# MAX3738ETG_MB.net
KiCad netlist of a schematic drawn in Altium Designer
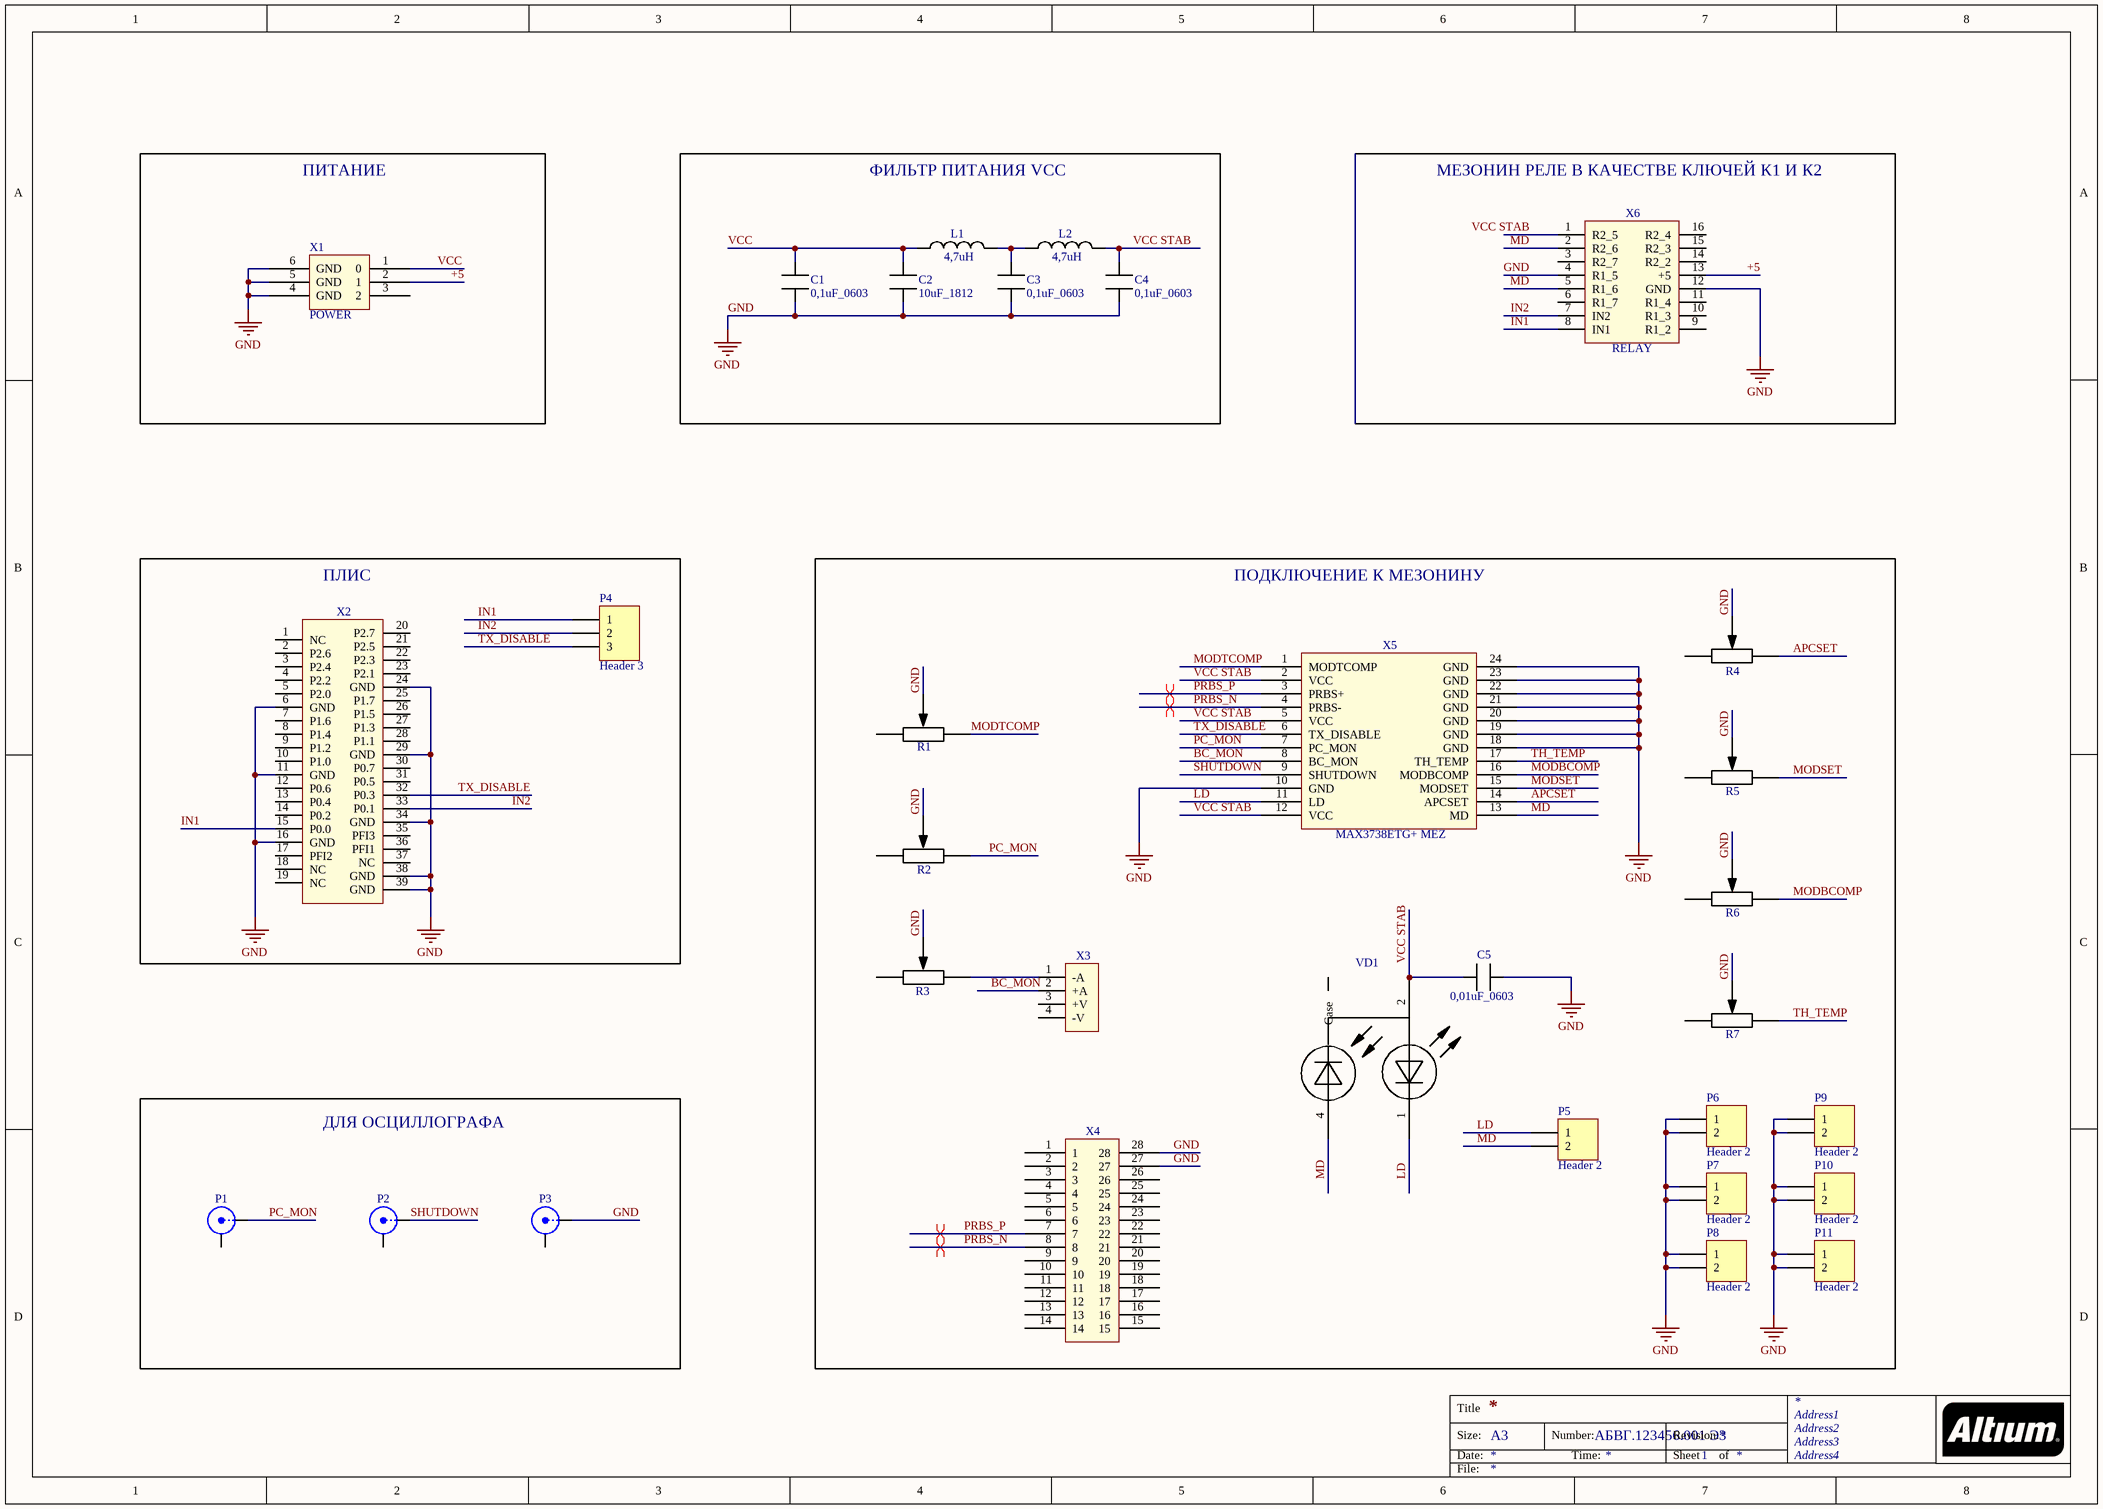
[diagram p0: MAX3738ETG+ MB.SchDoc]

(export (version "E")
  (design (tool "Eeschema 10.0.6"))
  (components
    (comp (ref "C1")
      (value "0,1uF_0603")
      (footprint "aab_Passive:CAP_0603")
      (libsource (lib "aab_Schlib") (part "CAP"))
    )
    (comp (ref "C2")
      (value "10uF_1812")
      (footprint "aab_Passive:CAP_1812")
      (libsource (lib "aab_Schlib") (part "CAP"))
    )
    (comp (ref "C3")
      (value "0,1uF_0603")
      (footprint "aab_Passive:CAP_0603")
      (libsource (lib "aab_Schlib") (part "CAP"))
    )
    (comp (ref "C4")
      (value "0,1uF_0603")
      (footprint "aab_Passive:CAP_0603")
      (libsource (lib "aab_Schlib") (part "CAP"))
    )
    (comp (ref "C5")
      (value "0,01uF_0603")
      (footprint "aab_Passive:CAP_0603")
      (libsource (lib "aab_Schlib") (part "CAP"))
    )
    (comp (ref "L1")
      (value "4,7uH")
      (footprint "aab_Passive:IND_0805")
      (libsource (lib "aab_Schlib") (part "IND"))
    )
    (comp (ref "L2")
      (value "4,7uH")
      (footprint "aab_Passive:IND_0805")
      (libsource (lib "aab_Schlib") (part "IND"))
    )
    (comp (ref "P1")
      (value "BNC")
      (footprint "BNC_RA CON")
      (description "BNC Elbow Connector")
      (fields (field (name "PUBLISHER") "Altium Limited"))
      (libsource (lib "Miscellaneous Connectors") (part "BNC"))
    )
    (comp (ref "P2")
      (value "BNC")
      (footprint "BNC_RA CON")
      (description "BNC Elbow Connector")
      (fields (field (name "PUBLISHER") "Altium Limited"))
      (libsource (lib "Miscellaneous Connectors") (part "BNC"))
    )
    (comp (ref "P3")
      (value "BNC")
      (footprint "BNC_RA CON")
      (description "BNC Elbow Connector")
      (fields (field (name "PUBLISHER") "Altium Limited"))
      (libsource (lib "Miscellaneous Connectors") (part "BNC"))
    )
    (comp (ref "P4")
      (value "Header 3")
      (footprint "HDR1X3")
      (description "Header, 3-Pin")
      (fields (field (name "PUBLISHER") "Altium Limited"))
      (libsource (lib "Miscellaneous Connectors") (part "Header 3"))
    )
    (comp (ref "P5")
      (value "Header 2")
      (footprint "HDR1X2")
      (description "Header, 2-Pin")
      (fields (field (name "PUBLISHER") "Altium Limited"))
      (libsource (lib "Miscellaneous Connectors") (part "Header 2"))
    )
    (comp (ref "P6")
      (value "Header 2")
      (footprint "HDR1X2")
      (description "Header, 2-Pin")
      (fields (field (name "PUBLISHER") "Altium Limited"))
      (libsource (lib "Miscellaneous Connectors") (part "Header 2"))
    )
    (comp (ref "P7")
      (value "Header 2")
      (footprint "HDR1X2")
      (description "Header, 2-Pin")
      (fields (field (name "PUBLISHER") "Altium Limited"))
      (libsource (lib "Miscellaneous Connectors") (part "Header 2"))
    )
    (comp (ref "P8")
      (value "Header 2")
      (footprint "HDR1X2")
      (description "Header, 2-Pin")
      (fields (field (name "PUBLISHER") "Altium Limited"))
      (libsource (lib "Miscellaneous Connectors") (part "Header 2"))
    )
    (comp (ref "P9")
      (value "Header 2")
      (footprint "HDR1X2")
      (description "Header, 2-Pin")
      (fields (field (name "PUBLISHER") "Altium Limited"))
      (libsource (lib "Miscellaneous Connectors") (part "Header 2"))
    )
    (comp (ref "P10")
      (value "Header 2")
      (footprint "HDR1X2")
      (description "Header, 2-Pin")
      (fields (field (name "PUBLISHER") "Altium Limited"))
      (libsource (lib "Miscellaneous Connectors") (part "Header 2"))
    )
    (comp (ref "P11")
      (value "Header 2")
      (footprint "HDR1X2")
      (description "Header, 2-Pin")
      (fields (field (name "PUBLISHER") "Altium Limited"))
      (libsource (lib "Miscellaneous Connectors") (part "Header 2"))
    )
    (comp (ref "R1")
      (value "RES 3266W")
      (footprint "aab_Passive:RES 3266W")
      (libsource (lib "aab_Schlib") (part "RES 3266W"))
    )
    (comp (ref "R2")
      (value "RES 3266W")
      (footprint "aab_Passive:RES 3266W")
      (libsource (lib "aab_Schlib") (part "RES 3266W"))
    )
    (comp (ref "R3")
      (value "RES 3266W")
      (footprint "aab_Passive:RES 3266W")
      (libsource (lib "aab_Schlib") (part "RES 3266W"))
    )
    (comp (ref "R4")
      (value "RES 3266W")
      (footprint "aab_Passive:RES 3266W")
      (libsource (lib "aab_Schlib") (part "RES 3266W"))
    )
    (comp (ref "R5")
      (value "RES 3266W")
      (footprint "aab_Passive:RES 3266W")
      (libsource (lib "aab_Schlib") (part "RES 3266W"))
    )
    (comp (ref "R6")
      (value "RES 3266W")
      (footprint "aab_Passive:RES 3266W")
      (libsource (lib "aab_Schlib") (part "RES 3266W"))
    )
    (comp (ref "R7")
      (value "RES 3266W")
      (footprint "aab_Passive:RES 3266W")
      (libsource (lib "aab_Schlib") (part "RES 3266W"))
    )
    (comp (ref "VD1")
      (value "LD with MD")
      (footprint "vpl_Passive:AMP_VOLTMETER")
      (libsource (lib "aab_Schlib") (part "LD with MD"))
    )
    (comp (ref "X1") (value "POWER") (footprint "POWER") (libsource (lib "vpl_Schlib") (part "POWER")))
    (comp (ref "X2")
      (value "CHEAP_CON_37_FEMALE")
      (footprint "CHEAP_CONN_FEMALE")
      (libsource (lib "vpl_Schlib") (part "CHEAP_CON_37_FEMALE"))
    )
    (comp (ref "X3")
      (value "AMPVOLT")
      (footprint "AMP_VOLTMETER")
      (libsource (lib "vpl_Schlib") (part "AMP_VOLTMETER"))
    )
    (comp (ref "X4")
      (value "DHR-26F")
      (footprint "aab_Passive:DHR-26F")
      (libsource (lib "aab_Schlib") (part "DHR-26F"))
    )
    (comp (ref "X5")
      (value "MAX3738ETG+ MEZ")
      (footprint "aab_Active:MAX3738ETG+ MEZ")
      (libsource (lib "aab_Schlib") (part "MAX3738ETG+ MEZ"))
    )
    (comp (ref "X6")
      (value "RELAY")
      (footprint "RELAY_MODULE")
      (libsource (lib "vpl_Schlib") (part "MEZON_RELAY"))
    )
  )
  (nets
    (net (code "1") (name "/+5") (class "Default")
      (node (ref "X1") (pin "2") (pinfunction "1_2") (pintype "passive"))
      (node (ref "X6") (pin "13") (pinfunction "+5_13") (pintype "passive"))
    )
    (net (code "2") (name "/APCSET") (class "Default")
      (node (ref "R4") (pin "3") (pinfunction "3_3") (pintype "passive"))
      (node (ref "X5") (pin "14") (pinfunction "APCSET_14") (pintype "passive"))
    )
    (net (code "3") (name "/BC_MON") (class "Default")
      (node (ref "X3") (pin "2") (pinfunction "+A_2") (pintype "passive"))
      (node (ref "X5") (pin "8") (pinfunction "BC_MON_8") (pintype "passive"))
    )
    (net (code "4") (name "/IN1") (class "Default")
      (node (ref "P4") (pin "1") (pinfunction "1_1") (pintype "passive"))
      (node (ref "X2") (pin "15") (pinfunction "P0.0_15") (pintype "passive"))
      (node (ref "X6") (pin "8") (pinfunction "IN1_8") (pintype "passive"))
    )
    (net (code "5") (name "/IN2") (class "Default")
      (node (ref "P4") (pin "2") (pinfunction "2_2") (pintype "passive"))
      (node (ref "X2") (pin "33") (pinfunction "P0.1_33") (pintype "passive"))
      (node (ref "X6") (pin "7") (pinfunction "IN2_7") (pintype "passive"))
    )
    (net (code "6") (name "/LD") (class "Default")
      (node (ref "P5") (pin "1") (pinfunction "1_1") (pintype "passive"))
      (node (ref "VD1") (pin "1") (pinfunction "1_1") (pintype "passive"))
      (node (ref "X5") (pin "11") (pinfunction "LD_11") (pintype "passive"))
    )
    (net (code "7") (name "/MD") (class "Default")
      (node (ref "P5") (pin "2") (pinfunction "2_2") (pintype "passive"))
      (node (ref "VD1") (pin "4") (pinfunction "4_4") (pintype "passive"))
      (node (ref "X5") (pin "13") (pinfunction "MD_13") (pintype "passive"))
      (node (ref "X6") (pin "2") (pinfunction "R2_6_2") (pintype "passive"))
      (node (ref "X6") (pin "5") (pinfunction "R1_6_5") (pintype "passive"))
    )
    (net (code "8") (name "/MODBCOMP") (class "Default")
      (node (ref "R6") (pin "3") (pinfunction "3_3") (pintype "passive"))
      (node (ref "X5") (pin "16") (pinfunction "MODBCOMP_16") (pintype "passive"))
    )
    (net (code "9") (name "/MODSET") (class "Default")
      (node (ref "R5") (pin "3") (pinfunction "3_3") (pintype "passive"))
      (node (ref "X5") (pin "15") (pinfunction "MODSET_15") (pintype "passive"))
    )
    (net (code "10") (name "/MODTCOMP") (class "Default")
      (node (ref "R1") (pin "3") (pinfunction "3_3") (pintype "passive"))
      (node (ref "X5") (pin "1") (pinfunction "MODTCOMP_1") (pintype "passive"))
    )
    (net (code "11") (name "/PC_MON") (class "Default")
      (node (ref "P1") (pin "1") (pinfunction "X_1") (pintype "passive"))
      (node (ref "R2") (pin "3") (pinfunction "3_3") (pintype "passive"))
      (node (ref "X5") (pin "7") (pinfunction "PC_MON_7") (pintype "passive"))
    )
    (net (code "12") (name "/PRBS_N") (class "Default")
      (node (ref "X4") (pin "8") (pinfunction "8_8") (pintype "passive"))
      (node (ref "X5") (pin "4") (pinfunction "PRBS-_4") (pintype "passive"))
    )
    (net (code "13") (name "/PRBS_P") (class "Default")
      (node (ref "X4") (pin "7") (pinfunction "7_7") (pintype "passive"))
      (node (ref "X5") (pin "3") (pinfunction "PRBS+_3") (pintype "passive"))
    )
    (net (code "14") (name "/SHUTDOWN") (class "Default")
      (node (ref "P2") (pin "1") (pinfunction "X_1") (pintype "passive"))
      (node (ref "X5") (pin "9") (pinfunction "SHUTDOWN_9") (pintype "passive"))
    )
    (net (code "15") (name "/TH_TEMP") (class "Default")
      (node (ref "R7") (pin "3") (pinfunction "3_3") (pintype "passive"))
      (node (ref "X5") (pin "17") (pinfunction "TH_TEMP_17") (pintype "passive"))
    )
    (net (code "16") (name "/TX_DISABLE") (class "Default")
      (node (ref "P4") (pin "3") (pinfunction "3_3") (pintype "passive"))
      (node (ref "X2") (pin "32") (pinfunction "P0.3_32") (pintype "passive"))
      (node (ref "X5") (pin "6") (pinfunction "TX_DISABLE_6") (pintype "passive"))
    )
    (net (code "17") (name "/VCC") (class "Default")
      (node (ref "C1") (pin "2") (pinfunction "2_2") (pintype "passive"))
      (node (ref "C2") (pin "2") (pinfunction "2_2") (pintype "passive"))
      (node (ref "L1") (pin "1") (pinfunction "1_1") (pintype "passive"))
      (node (ref "X1") (pin "1") (pinfunction "0_1") (pintype "passive"))
    )
    (net (code "18") (name "/VCC STAB") (class "Default")
      (node (ref "C4") (pin "2") (pinfunction "2_2") (pintype "passive"))
      (node (ref "C5") (pin "2") (pinfunction "2_2") (pintype "passive"))
      (node (ref "L2") (pin "2") (pinfunction "2_2") (pintype "passive"))
      (node (ref "VD1") (pin "2") (pinfunction "2_2") (pintype "passive"))
      (node (ref "X5") (pin "12") (pinfunction "VCC_12") (pintype "passive"))
      (node (ref "X5") (pin "2") (pinfunction "VCC_2") (pintype "passive"))
      (node (ref "X5") (pin "5") (pinfunction "VCC_5") (pintype "passive"))
      (node (ref "X6") (pin "1") (pinfunction "R2_5_1") (pintype "passive"))
    )
    (net (code "19") (name "GND") (class "Default")
      (node (ref "C1") (pin "1") (pinfunction "1_1") (pintype "passive"))
      (node (ref "C2") (pin "1") (pinfunction "1_1") (pintype "passive"))
      (node (ref "C3") (pin "1") (pinfunction "1_1") (pintype "passive"))
      (node (ref "C4") (pin "1") (pinfunction "1_1") (pintype "passive"))
      (node (ref "C5") (pin "1") (pinfunction "1_1") (pintype "passive"))
      (node (ref "P10") (pin "1") (pinfunction "1_1") (pintype "passive"))
      (node (ref "P10") (pin "2") (pinfunction "2_2") (pintype "passive"))
      (node (ref "P11") (pin "1") (pinfunction "1_1") (pintype "passive"))
      (node (ref "P11") (pin "2") (pinfunction "2_2") (pintype "passive"))
      (node (ref "P3") (pin "1") (pinfunction "X_1") (pintype "passive"))
      (node (ref "P6") (pin "1") (pinfunction "1_1") (pintype "passive"))
      (node (ref "P6") (pin "2") (pinfunction "2_2") (pintype "passive"))
      (node (ref "P7") (pin "1") (pinfunction "1_1") (pintype "passive"))
      (node (ref "P7") (pin "2") (pinfunction "2_2") (pintype "passive"))
      (node (ref "P8") (pin "1") (pinfunction "1_1") (pintype "passive"))
      (node (ref "P8") (pin "2") (pinfunction "2_2") (pintype "passive"))
      (node (ref "P9") (pin "1") (pinfunction "1_1") (pintype "passive"))
      (node (ref "P9") (pin "2") (pinfunction "2_2") (pintype "passive"))
      (node (ref "R1") (pin "2") (pinfunction "2_2") (pintype "passive"))
      (node (ref "R2") (pin "2") (pinfunction "2_2") (pintype "passive"))
      (node (ref "R3") (pin "2") (pinfunction "2_2") (pintype "passive"))
      (node (ref "R4") (pin "2") (pinfunction "2_2") (pintype "passive"))
      (node (ref "R5") (pin "2") (pinfunction "2_2") (pintype "passive"))
      (node (ref "R6") (pin "2") (pinfunction "2_2") (pintype "passive"))
      (node (ref "R7") (pin "2") (pinfunction "2_2") (pintype "passive"))
      (node (ref "X1") (pin "4") (pinfunction "GND_4") (pintype "passive"))
      (node (ref "X1") (pin "5") (pinfunction "GND_5") (pintype "passive"))
      (node (ref "X1") (pin "6") (pinfunction "GND_6") (pintype "passive"))
      (node (ref "X2") (pin "11") (pinfunction "GND_11") (pintype "passive"))
      (node (ref "X2") (pin "16") (pinfunction "GND_16") (pintype "passive"))
      (node (ref "X2") (pin "24") (pinfunction "GND_24") (pintype "passive"))
      (node (ref "X2") (pin "29") (pinfunction "GND_29") (pintype "passive"))
      (node (ref "X2") (pin "34") (pinfunction "GND_34") (pintype "passive"))
      (node (ref "X2") (pin "38") (pinfunction "GND_38") (pintype "passive"))
      (node (ref "X2") (pin "39") (pinfunction "GND_39") (pintype "passive"))
      (node (ref "X2") (pin "6") (pinfunction "GND_6") (pintype "passive"))
      (node (ref "X4") (pin "27") (pinfunction "27_27") (pintype "passive"))
      (node (ref "X4") (pin "28") (pinfunction "28_28") (pintype "passive"))
      (node (ref "X5") (pin "10") (pinfunction "GND_10") (pintype "passive"))
      (node (ref "X5") (pin "18") (pinfunction "GND_18") (pintype "passive"))
      (node (ref "X5") (pin "19") (pinfunction "GND_19") (pintype "passive"))
      (node (ref "X5") (pin "20") (pinfunction "GND_20") (pintype "passive"))
      (node (ref "X5") (pin "21") (pinfunction "GND_21") (pintype "passive"))
      (node (ref "X5") (pin "22") (pinfunction "GND_22") (pintype "passive"))
      (node (ref "X5") (pin "23") (pinfunction "GND_23") (pintype "passive"))
      (node (ref "X5") (pin "24") (pinfunction "GND_24") (pintype "passive"))
      (node (ref "X6") (pin "12") (pinfunction "GND_12") (pintype "passive"))
      (node (ref "X6") (pin "4") (pinfunction "R1_5_4") (pintype "passive"))
    )
    (net (code "20") (name "Net-(C3-Pad2)") (class "Default")
      (node (ref "C3") (pin "2") (pinfunction "2_2") (pintype "passive"))
      (node (ref "L1") (pin "2") (pinfunction "2_2") (pintype "passive"))
      (node (ref "L2") (pin "1") (pinfunction "1_1") (pintype "passive"))
    )
    (net (code "21") (name "Net-(X3--A)") (class "Default")
      (node (ref "R3") (pin "3") (pinfunction "3_3") (pintype "passive"))
      (node (ref "X3") (pin "1") (pinfunction "-A_1") (pintype "passive"))
    )
    (net (code "22") (name "unconnected-(P1-Y-Pad2)") (class "Default")
      (node (ref "P1") (pin "2") (pinfunction "Y_2") (pintype "passive"))
    )
    (net (code "23") (name "unconnected-(P2-Y-Pad2)") (class "Default")
      (node (ref "P2") (pin "2") (pinfunction "Y_2") (pintype "passive"))
    )
    (net (code "24") (name "unconnected-(P3-Y-Pad2)") (class "Default")
      (node (ref "P3") (pin "2") (pinfunction "Y_2") (pintype "passive"))
    )
    (net (code "25") (name "unconnected-(R1-Pad1)") (class "Default")
      (node (ref "R1") (pin "1") (pinfunction "1_1") (pintype "passive"))
    )
    (net (code "26") (name "unconnected-(R2-Pad1)") (class "Default")
      (node (ref "R2") (pin "1") (pinfunction "1_1") (pintype "passive"))
    )
    (net (code "27") (name "unconnected-(R3-Pad1)") (class "Default")
      (node (ref "R3") (pin "1") (pinfunction "1_1") (pintype "passive"))
    )
    (net (code "28") (name "unconnected-(R4-Pad1)") (class "Default")
      (node (ref "R4") (pin "1") (pinfunction "1_1") (pintype "passive"))
    )
    (net (code "29") (name "unconnected-(R5-Pad1)") (class "Default")
      (node (ref "R5") (pin "1") (pinfunction "1_1") (pintype "passive"))
    )
    (net (code "30") (name "unconnected-(R6-Pad1)") (class "Default")
      (node (ref "R6") (pin "1") (pinfunction "1_1") (pintype "passive"))
    )
    (net (code "31") (name "unconnected-(R7-Pad1)") (class "Default")
      (node (ref "R7") (pin "1") (pinfunction "1_1") (pintype "passive"))
    )
    (net (code "32") (name "unconnected-(VD1-Case-Pad3)") (class "Default")
      (node (ref "VD1") (pin "3") (pinfunction "Case_3") (pintype "passive"))
    )
    (net (code "33") (name "unconnected-(X1-2-Pad3)") (class "Default")
      (node (ref "X1") (pin "3") (pinfunction "2_3") (pintype "passive"))
    )
    (net (code "34") (name "unconnected-(X2-NC-Pad1)") (class "Default")
      (node (ref "X2") (pin "1") (pinfunction "NC_1") (pintype "passive"))
    )
    (net (code "35") (name "unconnected-(X2-NC-Pad18)") (class "Default")
      (node (ref "X2") (pin "18") (pinfunction "NC_18") (pintype "passive"))
    )
    (net (code "36") (name "unconnected-(X2-NC-Pad19)") (class "Default")
      (node (ref "X2") (pin "19") (pinfunction "NC_19") (pintype "passive"))
    )
    (net (code "37") (name "unconnected-(X2-NC-Pad37)") (class "Default")
      (node (ref "X2") (pin "37") (pinfunction "NC_37") (pintype "passive"))
    )
    (net (code "38") (name "unconnected-(X2-P0.2-Pad14)") (class "Default")
      (node (ref "X2") (pin "14") (pinfunction "P0.2_14") (pintype "passive"))
    )
    (net (code "39") (name "unconnected-(X2-P0.4-Pad13)") (class "Default")
      (node (ref "X2") (pin "13") (pinfunction "P0.4_13") (pintype "passive"))
    )
    (net (code "40") (name "unconnected-(X2-P0.5-Pad31)") (class "Default")
      (node (ref "X2") (pin "31") (pinfunction "P0.5_31") (pintype "passive"))
    )
    (net (code "41") (name "unconnected-(X2-P0.6-Pad12)") (class "Default")
      (node (ref "X2") (pin "12") (pinfunction "P0.6_12") (pintype "passive"))
    )
    (net (code "42") (name "unconnected-(X2-P0.7-Pad30)") (class "Default")
      (node (ref "X2") (pin "30") (pinfunction "P0.7_30") (pintype "passive"))
    )
    (net (code "43") (name "unconnected-(X2-P1.0-Pad10)") (class "Default")
      (node (ref "X2") (pin "10") (pinfunction "P1.0_10") (pintype "passive"))
    )
    (net (code "44") (name "unconnected-(X2-P1.1-Pad28)") (class "Default")
      (node (ref "X2") (pin "28") (pinfunction "P1.1_28") (pintype "passive"))
    )
    (net (code "45") (name "unconnected-(X2-P1.2-Pad9)") (class "Default")
      (node (ref "X2") (pin "9") (pinfunction "P1.2_9") (pintype "passive"))
    )
    (net (code "46") (name "unconnected-(X2-P1.3-Pad27)") (class "Default")
      (node (ref "X2") (pin "27") (pinfunction "P1.3_27") (pintype "passive"))
    )
    (net (code "47") (name "unconnected-(X2-P1.4-Pad8)") (class "Default")
      (node (ref "X2") (pin "8") (pinfunction "P1.4_8") (pintype "passive"))
    )
    (net (code "48") (name "unconnected-(X2-P1.5-Pad26)") (class "Default")
      (node (ref "X2") (pin "26") (pinfunction "P1.5_26") (pintype "passive"))
    )
    (net (code "49") (name "unconnected-(X2-P1.6-Pad7)") (class "Default")
      (node (ref "X2") (pin "7") (pinfunction "P1.6_7") (pintype "passive"))
    )
    (net (code "50") (name "unconnected-(X2-P1.7-Pad25)") (class "Default")
      (node (ref "X2") (pin "25") (pinfunction "P1.7_25") (pintype "passive"))
    )
    (net (code "51") (name "unconnected-(X2-P2.0-Pad5)") (class "Default")
      (node (ref "X2") (pin "5") (pinfunction "P2.0_5") (pintype "passive"))
    )
    (net (code "52") (name "unconnected-(X2-P2.1-Pad23)") (class "Default")
      (node (ref "X2") (pin "23") (pinfunction "P2.1_23") (pintype "passive"))
    )
    (net (code "53") (name "unconnected-(X2-P2.2-Pad4)") (class "Default")
      (node (ref "X2") (pin "4") (pinfunction "P2.2_4") (pintype "passive"))
    )
    (net (code "54") (name "unconnected-(X2-P2.3-Pad22)") (class "Default")
      (node (ref "X2") (pin "22") (pinfunction "P2.3_22") (pintype "passive"))
    )
    (net (code "55") (name "unconnected-(X2-P2.4-Pad3)") (class "Default")
      (node (ref "X2") (pin "3") (pinfunction "P2.4_3") (pintype "passive"))
    )
    (net (code "56") (name "unconnected-(X2-P2.5-Pad21)") (class "Default")
      (node (ref "X2") (pin "21") (pinfunction "P2.5_21") (pintype "passive"))
    )
    (net (code "57") (name "unconnected-(X2-P2.6-Pad2)") (class "Default")
      (node (ref "X2") (pin "2") (pinfunction "P2.6_2") (pintype "passive"))
    )
    (net (code "58") (name "unconnected-(X2-P2.7-Pad20)") (class "Default")
      (node (ref "X2") (pin "20") (pinfunction "P2.7_20") (pintype "passive"))
    )
    (net (code "59") (name "unconnected-(X2-PFI1-Pad36)") (class "Default")
      (node (ref "X2") (pin "36") (pinfunction "PFI1_36") (pintype "passive"))
    )
    (net (code "60") (name "unconnected-(X2-PFI2-Pad17)") (class "Default")
      (node (ref "X2") (pin "17") (pinfunction "PFI2_17") (pintype "passive"))
    )
    (net (code "61") (name "unconnected-(X2-PFI3-Pad35)") (class "Default")
      (node (ref "X2") (pin "35") (pinfunction "PFI3_35") (pintype "passive"))
    )
    (net (code "62") (name "unconnected-(X3-+V-Pad3)") (class "Default")
      (node (ref "X3") (pin "3") (pinfunction "+V_3") (pintype "passive"))
    )
    (net (code "63") (name "unconnected-(X3--V-Pad4)") (class "Default")
      (node (ref "X3") (pin "4") (pinfunction "-V_4") (pintype "passive"))
    )
    (net (code "64") (name "unconnected-(X4-Pad1)") (class "Default")
      (node (ref "X4") (pin "1") (pinfunction "1_1") (pintype "passive"))
    )
    (net (code "65") (name "unconnected-(X4-Pad2)") (class "Default")
      (node (ref "X4") (pin "2") (pinfunction "2_2") (pintype "passive"))
    )
    (net (code "66") (name "unconnected-(X4-Pad3)") (class "Default")
      (node (ref "X4") (pin "3") (pinfunction "3_3") (pintype "passive"))
    )
    (net (code "67") (name "unconnected-(X4-Pad4)") (class "Default")
      (node (ref "X4") (pin "4") (pinfunction "4_4") (pintype "passive"))
    )
    (net (code "68") (name "unconnected-(X4-Pad5)") (class "Default")
      (node (ref "X4") (pin "5") (pinfunction "5_5") (pintype "passive"))
    )
    (net (code "69") (name "unconnected-(X4-Pad6)") (class "Default")
      (node (ref "X4") (pin "6") (pinfunction "6_6") (pintype "passive"))
    )
    (net (code "70") (name "unconnected-(X4-Pad9)") (class "Default")
      (node (ref "X4") (pin "9") (pinfunction "9_9") (pintype "passive"))
    )
    (net (code "71") (name "unconnected-(X4-Pad10)") (class "Default")
      (node (ref "X4") (pin "10") (pinfunction "10_10") (pintype "passive"))
    )
    (net (code "72") (name "unconnected-(X4-Pad11)") (class "Default")
      (node (ref "X4") (pin "11") (pinfunction "11_11") (pintype "passive"))
    )
    (net (code "73") (name "unconnected-(X4-Pad12)") (class "Default")
      (node (ref "X4") (pin "12") (pinfunction "12_12") (pintype "passive"))
    )
    (net (code "74") (name "unconnected-(X4-Pad13)") (class "Default")
      (node (ref "X4") (pin "13") (pinfunction "13_13") (pintype "passive"))
    )
    (net (code "75") (name "unconnected-(X4-Pad14)") (class "Default")
      (node (ref "X4") (pin "14") (pinfunction "14_14") (pintype "passive"))
    )
    (net (code "76") (name "unconnected-(X4-Pad15)") (class "Default")
      (node (ref "X4") (pin "15") (pinfunction "15_15") (pintype "passive"))
    )
    (net (code "77") (name "unconnected-(X4-Pad16)") (class "Default")
      (node (ref "X4") (pin "16") (pinfunction "16_16") (pintype "passive"))
    )
    (net (code "78") (name "unconnected-(X4-Pad17)") (class "Default")
      (node (ref "X4") (pin "17") (pinfunction "17_17") (pintype "passive"))
    )
    (net (code "79") (name "unconnected-(X4-Pad18)") (class "Default")
      (node (ref "X4") (pin "18") (pinfunction "18_18") (pintype "passive"))
    )
    (net (code "80") (name "unconnected-(X4-Pad19)") (class "Default")
      (node (ref "X4") (pin "19") (pinfunction "19_19") (pintype "passive"))
    )
    (net (code "81") (name "unconnected-(X4-Pad20)") (class "Default")
      (node (ref "X4") (pin "20") (pinfunction "20_20") (pintype "passive"))
    )
    (net (code "82") (name "unconnected-(X4-Pad21)") (class "Default")
      (node (ref "X4") (pin "21") (pinfunction "21_21") (pintype "passive"))
    )
    (net (code "83") (name "unconnected-(X4-Pad22)") (class "Default")
      (node (ref "X4") (pin "22") (pinfunction "22_22") (pintype "passive"))
    )
    (net (code "84") (name "unconnected-(X4-Pad23)") (class "Default")
      (node (ref "X4") (pin "23") (pinfunction "23_23") (pintype "passive"))
    )
    (net (code "85") (name "unconnected-(X4-Pad24)") (class "Default")
      (node (ref "X4") (pin "24") (pinfunction "24_24") (pintype "passive"))
    )
    (net (code "86") (name "unconnected-(X4-Pad25)") (class "Default")
      (node (ref "X4") (pin "25") (pinfunction "25_25") (pintype "passive"))
    )
    (net (code "87") (name "unconnected-(X4-Pad26)") (class "Default")
      (node (ref "X4") (pin "26") (pinfunction "26_26") (pintype "passive"))
    )
    (net (code "88") (name "unconnected-(X6-R1_2-Pad9)") (class "Default")
      (node (ref "X6") (pin "9") (pinfunction "R1_2_9") (pintype "passive"))
    )
    (net (code "89") (name "unconnected-(X6-R1_3-Pad10)") (class "Default")
      (node (ref "X6") (pin "10") (pinfunction "R1_3_10") (pintype "passive"))
    )
    (net (code "90") (name "unconnected-(X6-R1_4-Pad11)") (class "Default")
      (node (ref "X6") (pin "11") (pinfunction "R1_4_11") (pintype "passive"))
    )
    (net (code "91") (name "unconnected-(X6-R1_7-Pad6)") (class "Default")
      (node (ref "X6") (pin "6") (pinfunction "R1_7_6") (pintype "passive"))
    )
    (net (code "92") (name "unconnected-(X6-R2_2-Pad14)") (class "Default")
      (node (ref "X6") (pin "14") (pinfunction "R2_2_14") (pintype "passive"))
    )
    (net (code "93") (name "unconnected-(X6-R2_3-Pad15)") (class "Default")
      (node (ref "X6") (pin "15") (pinfunction "R2_3_15") (pintype "passive"))
    )
    (net (code "94") (name "unconnected-(X6-R2_4-Pad16)") (class "Default")
      (node (ref "X6") (pin "16") (pinfunction "R2_4_16") (pintype "passive"))
    )
    (net (code "95") (name "unconnected-(X6-R2_7-Pad3)") (class "Default")
      (node (ref "X6") (pin "3") (pinfunction "R2_7_3") (pintype "passive"))
    )
  )
)
